# Relay_Control.net
KiCad netlist of a schematic drawn in Altium Designer
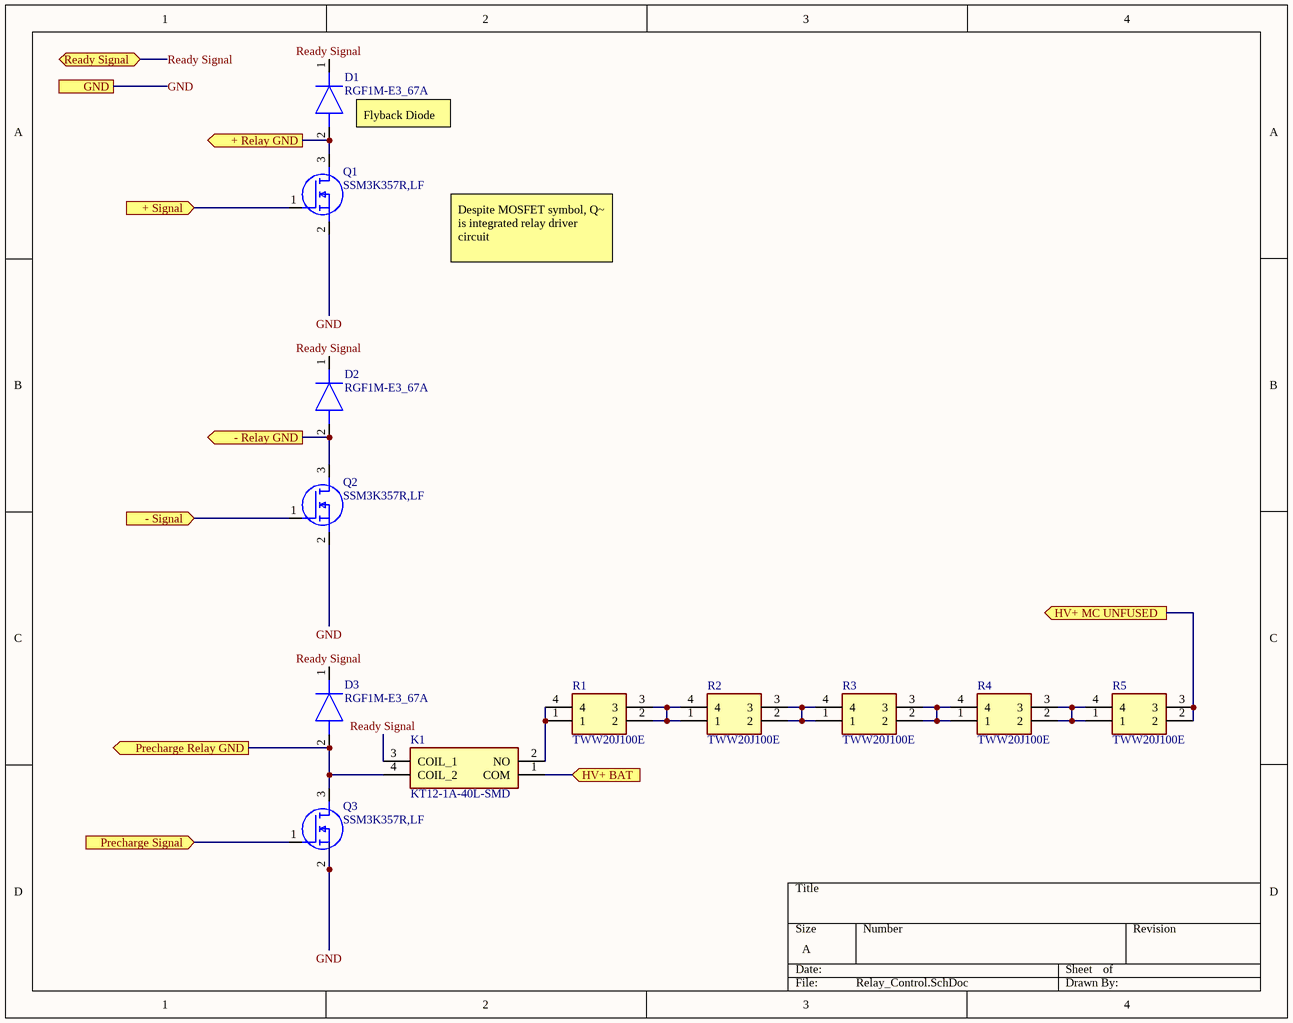
[diagram p0: Relay_Control.SchDoc]

(export (version "E")
  (design (tool "Eeschema 10.0.6"))
  (components
    (comp (ref "D1")
      (value "RGF1M-E3_67A")
      (footprint "SamacSys:DIOM5426X300N")
      (description "Diode")
      (fields
        (field (name "MANUFACTURER_PART_NUMBER") "RGF1M-E3/67A")
        (field (name "MOUSER PART NUMBER") "625-RGF1M-E3")
      )
      (libsource (lib "*") (part "RGF1M-E3_67A"))
    )
    (comp (ref "D2")
      (value "RGF1M-E3_67A")
      (footprint "SamacSys:DIOM5426X300N")
      (description "Diode")
      (fields
        (field (name "MANUFACTURER_PART_NUMBER") "RGF1M-E3/67A")
        (field (name "MOUSER PART NUMBER") "625-RGF1M-E3")
      )
      (libsource (lib "*") (part "RGF1M-E3_67A"))
    )
    (comp (ref "D3")
      (value "RGF1M-E3_67A")
      (footprint "SamacSys:DIOM5426X300N")
      (description "Diode")
      (fields
        (field (name "MANUFACTURER_PART_NUMBER") "RGF1M-E3/67A")
        (field (name "MOUSER PART NUMBER") "625-RGF1M-E3")
      )
      (libsource (lib "*") (part "RGF1M-E3_67A"))
    )
    (comp (ref "K1")
      (value "KT12-1A-40L-SMD")
      (footprint "SamacSys:KT121A40LSMD")
      (description "Relay or Contactor")
      (fields (field (name "MOUSER PART NUMBER") "876-KT12-1A-40L-SMD"))
      (libsource (lib "*") (part "KT12-1A-40L-SMD"))
    )
    (comp (ref "Q1")
      (value "SSM3K357R,LF")
      (footprint "SamacSys:SOTFL95P240X88-3N")
      (description "MOSFET (N-Channel)")
      (fields (field (name "MOUSER PART NUMBER") "757-SSM3K357RLF"))
      (libsource (lib "*") (part "SSM3K357R,LF"))
    )
    (comp (ref "Q2")
      (value "SSM3K357R,LF")
      (footprint "SamacSys:SOTFL95P240X88-3N")
      (description "MOSFET (N-Channel)")
      (fields (field (name "MOUSER PART NUMBER") "757-SSM3K357RLF"))
      (libsource (lib "*") (part "SSM3K357R,LF"))
    )
    (comp (ref "Q3")
      (value "SSM3K357R,LF")
      (footprint "SamacSys:SOTFL95P240X88-3N")
      (description "MOSFET (N-Channel)")
      (fields (field (name "MOUSER PART NUMBER") "757-SSM3K357RLF"))
      (libsource (lib "*") (part "SSM3K357R,LF"))
    )
    (comp (ref "R1")
      (value "TWW20J100E")
      (footprint "SamacSys:TWW20J100E")
      (description "Resistor")
      (fields (field (name "MOUSER PART NUMBER") "588-TWW20J100E"))
      (libsource (lib "*") (part "TWW20J100E"))
    )
    (comp (ref "R2")
      (value "TWW20J100E")
      (footprint "SamacSys:TWW20J100E")
      (description "Resistor")
      (fields (field (name "MOUSER PART NUMBER") "588-TWW20J100E"))
      (libsource (lib "*") (part "TWW20J100E"))
    )
    (comp (ref "R3")
      (value "TWW20J100E")
      (footprint "SamacSys:TWW20J100E")
      (description "Resistor")
      (fields (field (name "MOUSER PART NUMBER") "588-TWW20J100E"))
      (libsource (lib "*") (part "TWW20J100E"))
    )
    (comp (ref "R4")
      (value "TWW20J100E")
      (footprint "SamacSys:TWW20J100E")
      (description "Resistor")
      (fields (field (name "MOUSER PART NUMBER") "588-TWW20J100E"))
      (libsource (lib "*") (part "TWW20J100E"))
    )
    (comp (ref "R5")
      (value "TWW20J100E")
      (footprint "SamacSys:TWW20J100E")
      (description "Resistor")
      (fields (field (name "MOUSER PART NUMBER") "588-TWW20J100E"))
      (libsource (lib "*") (part "TWW20J100E"))
    )
  )
  (nets
    (net (code "1") (name "/+ Relay GND") (class "Default")
      (node (ref "D1") (pin "2") (pinfunction "A_2") (pintype "passive"))
      (node (ref "Q1") (pin "3") (pinfunction "D_3") (pintype "passive"))
    )
    (net (code "2") (name "/+ Signal") (class "Default")
      (node (ref "Q1") (pin "1") (pinfunction "G_1") (pintype "passive"))
    )
    (net (code "3") (name "/- Relay GND") (class "Default")
      (node (ref "D2") (pin "2") (pinfunction "A_2") (pintype "passive"))
      (node (ref "Q2") (pin "3") (pinfunction "D_3") (pintype "passive"))
    )
    (net (code "4") (name "/- Signal") (class "Default")
      (node (ref "Q2") (pin "1") (pinfunction "G_1") (pintype "passive"))
    )
    (net (code "5") (name "/GND") (class "Default")
      (node (ref "Q1") (pin "2") (pinfunction "S_2") (pintype "passive"))
      (node (ref "Q2") (pin "2") (pinfunction "S_2") (pintype "passive"))
      (node (ref "Q3") (pin "2") (pinfunction "S_2") (pintype "passive"))
    )
    (net (code "6") (name "/HV+ BAT") (class "Default")
      (node (ref "K1") (pin "1") (pinfunction "COM_1") (pintype "passive"))
    )
    (net (code "7") (name "/HV+ MC UNFUSED") (class "Default")
      (node (ref "R5") (pin "2") (pinfunction "2_2") (pintype "passive"))
      (node (ref "R5") (pin "3") (pinfunction "3_3") (pintype "passive"))
    )
    (net (code "8") (name "/Precharge Relay GND") (class "Default")
      (node (ref "D3") (pin "2") (pinfunction "A_2") (pintype "passive"))
      (node (ref "K1") (pin "4") (pinfunction "COIL_2_4") (pintype "passive"))
      (node (ref "Q3") (pin "3") (pinfunction "D_3") (pintype "passive"))
    )
    (net (code "9") (name "/Precharge Signal") (class "Default")
      (node (ref "Q3") (pin "1") (pinfunction "G_1") (pintype "passive"))
    )
    (net (code "10") (name "/Ready Signal") (class "Default")
      (node (ref "D1") (pin "1") (pinfunction "K_1") (pintype "passive"))
      (node (ref "D2") (pin "1") (pinfunction "K_1") (pintype "passive"))
      (node (ref "D3") (pin "1") (pinfunction "K_1") (pintype "passive"))
      (node (ref "K1") (pin "3") (pinfunction "COIL_1_3") (pintype "passive"))
    )
    (net (code "11") (name "Net-(K1-NO)") (class "Default")
      (node (ref "K1") (pin "2") (pinfunction "NO_2") (pintype "passive"))
      (node (ref "R1") (pin "1") (pinfunction "1_1") (pintype "passive"))
      (node (ref "R1") (pin "4") (pinfunction "4_4") (pintype "passive"))
    )
    (net (code "12") (name "Net-(R1-Pad2)") (class "Default")
      (node (ref "R1") (pin "2") (pinfunction "2_2") (pintype "passive"))
      (node (ref "R1") (pin "3") (pinfunction "3_3") (pintype "passive"))
      (node (ref "R2") (pin "1") (pinfunction "1_1") (pintype "passive"))
      (node (ref "R2") (pin "4") (pinfunction "4_4") (pintype "passive"))
    )
    (net (code "13") (name "Net-(R2-Pad2)") (class "Default")
      (node (ref "R2") (pin "2") (pinfunction "2_2") (pintype "passive"))
      (node (ref "R2") (pin "3") (pinfunction "3_3") (pintype "passive"))
      (node (ref "R3") (pin "1") (pinfunction "1_1") (pintype "passive"))
      (node (ref "R3") (pin "4") (pinfunction "4_4") (pintype "passive"))
    )
    (net (code "14") (name "Net-(R3-Pad2)") (class "Default")
      (node (ref "R3") (pin "2") (pinfunction "2_2") (pintype "passive"))
      (node (ref "R3") (pin "3") (pinfunction "3_3") (pintype "passive"))
      (node (ref "R4") (pin "1") (pinfunction "1_1") (pintype "passive"))
      (node (ref "R4") (pin "4") (pinfunction "4_4") (pintype "passive"))
    )
    (net (code "15") (name "Net-(R4-Pad2)") (class "Default")
      (node (ref "R4") (pin "2") (pinfunction "2_2") (pintype "passive"))
      (node (ref "R4") (pin "3") (pinfunction "3_3") (pintype "passive"))
      (node (ref "R5") (pin "1") (pinfunction "1_1") (pintype "passive"))
      (node (ref "R5") (pin "4") (pinfunction "4_4") (pintype "passive"))
    )
  )
)
